# mod_hw_tb6612.net
KiCad netlist of a schematic drawn in Altium Designer
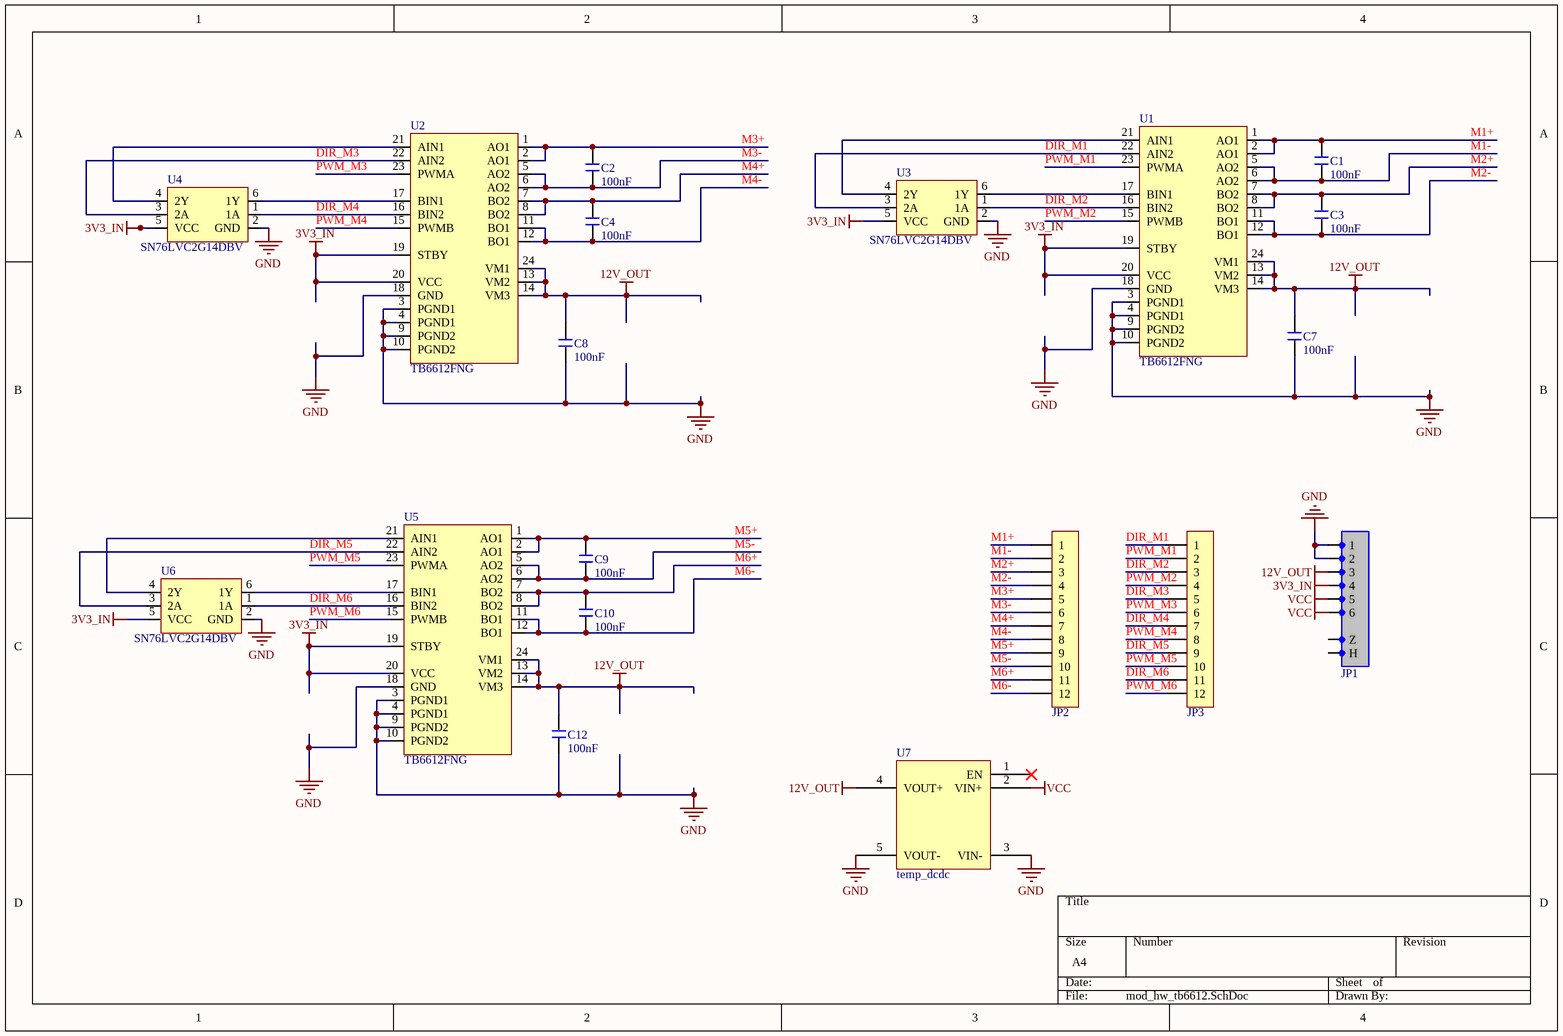
[diagram p0: mod_hw_tb6612.SchDoc]

(export (version "E")
  (design (tool "Eeschema 10.0.6"))
  (components
    (comp (ref "C1")
      (value "100nF")
      (footprint "C 0603_L")
      (description "无极性贴片电容")
      (fields (field (name "版权归属") "源创客"))
      (libsource (lib "3.2-电容") (part "C"))
    )
    (comp (ref "C2")
      (value "100nF")
      (footprint "C 0603_L")
      (description "无极性贴片电容")
      (fields (field (name "版权归属") "源创客"))
      (libsource (lib "3.2-电容") (part "C"))
    )
    (comp (ref "C3")
      (value "100nF")
      (footprint "C 0603_L")
      (description "无极性贴片电容")
      (fields (field (name "版权归属") "源创客"))
      (libsource (lib "3.2-电容") (part "C"))
    )
    (comp (ref "C4")
      (value "100nF")
      (footprint "C 0603_L")
      (description "无极性贴片电容")
      (fields (field (name "版权归属") "源创客"))
      (libsource (lib "3.2-电容") (part "C"))
    )
    (comp (ref "C7")
      (value "100nF")
      (footprint "C 1206_L")
      (description "无极性贴片电容")
      (fields (field (name "版权归属") "源创客"))
      (libsource (lib "3.2-电容") (part "C"))
    )
    (comp (ref "C8")
      (value "100nF")
      (footprint "C 1206_L")
      (description "无极性贴片电容")
      (fields (field (name "版权归属") "源创客"))
      (libsource (lib "3.2-电容") (part "C"))
    )
    (comp (ref "C9")
      (value "100nF")
      (footprint "C 0603_L")
      (description "无极性贴片电容")
      (fields (field (name "版权归属") "源创客"))
      (libsource (lib "3.2-电容") (part "C"))
    )
    (comp (ref "C10")
      (value "100nF")
      (footprint "C 0603_L")
      (description "无极性贴片电容")
      (fields (field (name "版权归属") "源创客"))
      (libsource (lib "3.2-电容") (part "C"))
    )
    (comp (ref "C12")
      (value "100nF")
      (footprint "C 1206_L")
      (description "无极性贴片电容")
      (fields (field (name "版权归属") "源创客"))
      (libsource (lib "3.2-电容") (part "C"))
    )
    (comp (ref "JP1")
      (value "HDR-1X6")
      (footprint "HDR2.54-M-LI-6P")
      (description "6P接插件")
      (fields (field (name "版权归属") "源创客"))
      (libsource (lib "14.6-接插件-脚距2.54") (part "Header 6"))
    )
    (comp (ref "JP2")
      (value "HDR-1X12")
      (footprint "HDR2.54-M-LI-12P")
      (description "12P接插件")
      (fields (field (name "版权归属") "源创客"))
      (libsource (lib "14.6-接插件-脚距2.54") (part "Header 12"))
    )
    (comp (ref "JP3")
      (value "HDR-1X12")
      (footprint "HDR2.54-M-LI-12P")
      (description "12P接插件")
      (fields (field (name "版权归属") "源创客"))
      (libsource (lib "14.6-接插件-脚距2.54") (part "Header 12"))
    )
    (comp (ref "U1")
      (value "TB6612FNG")
      (footprint "SSOP24_N")
      (libsource (lib "Schlib1") (part "Component_1"))
    )
    (comp (ref "U2")
      (value "TB6612FNG")
      (footprint "SSOP24_N")
      (libsource (lib "Schlib1") (part "Component_1"))
    )
    (comp (ref "U3")
      (value "SN76LVC2G14DBV")
      (footprint "SOT23-6N")
      (libsource (lib "Schlib1") (part "SN76LVC2G14DBV"))
    )
    (comp (ref "U4")
      (value "SN76LVC2G14DBV")
      (footprint "SOT23-6N")
      (libsource (lib "Schlib1") (part "SN76LVC2G14DBV"))
    )
    (comp (ref "U5")
      (value "TB6612FNG")
      (footprint "SSOP24_N")
      (libsource (lib "Schlib1") (part "Component_1"))
    )
    (comp (ref "U6")
      (value "SN76LVC2G14DBV")
      (footprint "SOT23-6N")
      (libsource (lib "Schlib1") (part "SN76LVC2G14DBV"))
    )
    (comp (ref "U7")
      (value "temp_dcdc")
      (footprint "TEMP_12V")
      (description "升降压模块")
      (libsource (lib "userLib") (part "temp_dcdc"))
    )
  )
  (nets
    (net (code "1") (name "/DIR_M1") (class "Default")
      (node (ref "JP3") (pin "1") (pinfunction "1_1") (pintype "passive"))
      (node (ref "U1") (pin "22") (pinfunction "AIN2_22") (pintype "passive"))
      (node (ref "U3") (pin "3") (pinfunction "2A_3") (pintype "passive"))
    )
    (net (code "2") (name "/DIR_M2") (class "Default")
      (node (ref "JP3") (pin "3") (pinfunction "3_3") (pintype "passive"))
      (node (ref "U1") (pin "16") (pinfunction "BIN2_16") (pintype "passive"))
      (node (ref "U3") (pin "1") (pinfunction "1A_1") (pintype "passive"))
    )
    (net (code "3") (name "/DIR_M3") (class "Default")
      (node (ref "JP3") (pin "5") (pinfunction "5_5") (pintype "passive"))
      (node (ref "U2") (pin "22") (pinfunction "AIN2_22") (pintype "passive"))
      (node (ref "U4") (pin "3") (pinfunction "2A_3") (pintype "passive"))
    )
    (net (code "4") (name "/DIR_M4") (class "Default")
      (node (ref "JP3") (pin "7") (pinfunction "7_7") (pintype "passive"))
      (node (ref "U2") (pin "16") (pinfunction "BIN2_16") (pintype "passive"))
      (node (ref "U4") (pin "1") (pinfunction "1A_1") (pintype "passive"))
    )
    (net (code "5") (name "/DIR_M5") (class "Default")
      (node (ref "JP3") (pin "9") (pinfunction "9_9") (pintype "passive"))
      (node (ref "U5") (pin "22") (pinfunction "AIN2_22") (pintype "passive"))
      (node (ref "U6") (pin "3") (pinfunction "2A_3") (pintype "passive"))
    )
    (net (code "6") (name "/DIR_M6") (class "Default")
      (node (ref "JP3") (pin "11") (pinfunction "11_11") (pintype "passive"))
      (node (ref "U5") (pin "16") (pinfunction "BIN2_16") (pintype "passive"))
      (node (ref "U6") (pin "1") (pinfunction "1A_1") (pintype "passive"))
    )
    (net (code "7") (name "/M1+") (class "Default")
      (node (ref "C1") (pin "2") (pinfunction "2_2") (pintype "passive"))
      (node (ref "JP2") (pin "1") (pinfunction "1_1") (pintype "passive"))
      (node (ref "U1") (pin "1") (pinfunction "AO1_1") (pintype "passive"))
      (node (ref "U1") (pin "2") (pinfunction "AO1_2") (pintype "passive"))
    )
    (net (code "8") (name "/M1-") (class "Default")
      (node (ref "C1") (pin "1") (pinfunction "1_1") (pintype "passive"))
      (node (ref "JP2") (pin "2") (pinfunction "2_2") (pintype "passive"))
      (node (ref "U1") (pin "5") (pinfunction "AO2_5") (pintype "passive"))
      (node (ref "U1") (pin "6") (pinfunction "AO2_6") (pintype "passive"))
    )
    (net (code "9") (name "/M2+") (class "Default")
      (node (ref "C3") (pin "2") (pinfunction "2_2") (pintype "passive"))
      (node (ref "JP2") (pin "3") (pinfunction "3_3") (pintype "passive"))
      (node (ref "U1") (pin "7") (pinfunction "BO2_7") (pintype "passive"))
      (node (ref "U1") (pin "8") (pinfunction "BO2_8") (pintype "passive"))
    )
    (net (code "10") (name "/M2-") (class "Default")
      (node (ref "C3") (pin "1") (pinfunction "1_1") (pintype "passive"))
      (node (ref "JP2") (pin "4") (pinfunction "4_4") (pintype "passive"))
      (node (ref "U1") (pin "11") (pinfunction "BO1_11") (pintype "passive"))
      (node (ref "U1") (pin "12") (pinfunction "BO1_12") (pintype "passive"))
    )
    (net (code "11") (name "/M3+") (class "Default")
      (node (ref "C2") (pin "2") (pinfunction "2_2") (pintype "passive"))
      (node (ref "JP2") (pin "5") (pinfunction "5_5") (pintype "passive"))
      (node (ref "U2") (pin "1") (pinfunction "AO1_1") (pintype "passive"))
      (node (ref "U2") (pin "2") (pinfunction "AO1_2") (pintype "passive"))
    )
    (net (code "12") (name "/M3-") (class "Default")
      (node (ref "C2") (pin "1") (pinfunction "1_1") (pintype "passive"))
      (node (ref "JP2") (pin "6") (pinfunction "6_6") (pintype "passive"))
      (node (ref "U2") (pin "5") (pinfunction "AO2_5") (pintype "passive"))
      (node (ref "U2") (pin "6") (pinfunction "AO2_6") (pintype "passive"))
    )
    (net (code "13") (name "/M4+") (class "Default")
      (node (ref "C4") (pin "2") (pinfunction "2_2") (pintype "passive"))
      (node (ref "JP2") (pin "7") (pinfunction "7_7") (pintype "passive"))
      (node (ref "U2") (pin "7") (pinfunction "BO2_7") (pintype "passive"))
      (node (ref "U2") (pin "8") (pinfunction "BO2_8") (pintype "passive"))
    )
    (net (code "14") (name "/M4-") (class "Default")
      (node (ref "C4") (pin "1") (pinfunction "1_1") (pintype "passive"))
      (node (ref "JP2") (pin "8") (pinfunction "8_8") (pintype "passive"))
      (node (ref "U2") (pin "11") (pinfunction "BO1_11") (pintype "passive"))
      (node (ref "U2") (pin "12") (pinfunction "BO1_12") (pintype "passive"))
    )
    (net (code "15") (name "/M5+") (class "Default")
      (node (ref "C9") (pin "2") (pinfunction "2_2") (pintype "passive"))
      (node (ref "JP2") (pin "9") (pinfunction "9_9") (pintype "passive"))
      (node (ref "U5") (pin "1") (pinfunction "AO1_1") (pintype "passive"))
      (node (ref "U5") (pin "2") (pinfunction "AO1_2") (pintype "passive"))
    )
    (net (code "16") (name "/M5-") (class "Default")
      (node (ref "C9") (pin "1") (pinfunction "1_1") (pintype "passive"))
      (node (ref "JP2") (pin "10") (pinfunction "10_10") (pintype "passive"))
      (node (ref "U5") (pin "5") (pinfunction "AO2_5") (pintype "passive"))
      (node (ref "U5") (pin "6") (pinfunction "AO2_6") (pintype "passive"))
    )
    (net (code "17") (name "/M6+") (class "Default")
      (node (ref "C10") (pin "2") (pinfunction "2_2") (pintype "passive"))
      (node (ref "JP2") (pin "11") (pinfunction "11_11") (pintype "passive"))
      (node (ref "U5") (pin "7") (pinfunction "BO2_7") (pintype "passive"))
      (node (ref "U5") (pin "8") (pinfunction "BO2_8") (pintype "passive"))
    )
    (net (code "18") (name "/M6-") (class "Default")
      (node (ref "C10") (pin "1") (pinfunction "1_1") (pintype "passive"))
      (node (ref "JP2") (pin "12") (pinfunction "12_12") (pintype "passive"))
      (node (ref "U5") (pin "11") (pinfunction "BO1_11") (pintype "passive"))
      (node (ref "U5") (pin "12") (pinfunction "BO1_12") (pintype "passive"))
    )
    (net (code "19") (name "/PWM_M1") (class "Default")
      (node (ref "JP3") (pin "2") (pinfunction "2_2") (pintype "passive"))
      (node (ref "U1") (pin "23") (pinfunction "PWMA_23") (pintype "passive"))
    )
    (net (code "20") (name "/PWM_M2") (class "Default")
      (node (ref "JP3") (pin "4") (pinfunction "4_4") (pintype "passive"))
      (node (ref "U1") (pin "15") (pinfunction "PWMB_15") (pintype "passive"))
    )
    (net (code "21") (name "/PWM_M3") (class "Default")
      (node (ref "JP3") (pin "6") (pinfunction "6_6") (pintype "passive"))
      (node (ref "U2") (pin "23") (pinfunction "PWMA_23") (pintype "passive"))
    )
    (net (code "22") (name "/PWM_M4") (class "Default")
      (node (ref "JP3") (pin "8") (pinfunction "8_8") (pintype "passive"))
      (node (ref "U2") (pin "15") (pinfunction "PWMB_15") (pintype "passive"))
    )
    (net (code "23") (name "/PWM_M5") (class "Default")
      (node (ref "JP3") (pin "10") (pinfunction "10_10") (pintype "passive"))
      (node (ref "U5") (pin "23") (pinfunction "PWMA_23") (pintype "passive"))
    )
    (net (code "24") (name "/PWM_M6") (class "Default")
      (node (ref "JP3") (pin "12") (pinfunction "12_12") (pintype "passive"))
      (node (ref "U5") (pin "15") (pinfunction "PWMB_15") (pintype "passive"))
    )
    (net (code "25") (name "3V3_IN") (class "Default")
      (node (ref "JP1") (pin "4") (pinfunction "4_4") (pintype "passive"))
      (node (ref "U1") (pin "19") (pinfunction "STBY_19") (pintype "passive"))
      (node (ref "U1") (pin "20") (pinfunction "VCC_20") (pintype "passive"))
      (node (ref "U2") (pin "19") (pinfunction "STBY_19") (pintype "passive"))
      (node (ref "U2") (pin "20") (pinfunction "VCC_20") (pintype "passive"))
      (node (ref "U3") (pin "5") (pinfunction "VCC_5") (pintype "passive"))
      (node (ref "U4") (pin "5") (pinfunction "VCC_5") (pintype "passive"))
      (node (ref "U5") (pin "19") (pinfunction "STBY_19") (pintype "passive"))
      (node (ref "U5") (pin "20") (pinfunction "VCC_20") (pintype "passive"))
      (node (ref "U6") (pin "5") (pinfunction "VCC_5") (pintype "passive"))
    )
    (net (code "26") (name "12V_OUT") (class "Default")
      (node (ref "C12") (pin "2") (pinfunction "2_2") (pintype "passive"))
      (node (ref "C7") (pin "2") (pinfunction "2_2") (pintype "passive"))
      (node (ref "C8") (pin "2") (pinfunction "2_2") (pintype "passive"))
      (node (ref "JP1") (pin "3") (pinfunction "3_3") (pintype "passive"))
      (node (ref "U1") (pin "13") (pinfunction "VM2_13") (pintype "passive"))
      (node (ref "U1") (pin "14") (pinfunction "VM3_14") (pintype "passive"))
      (node (ref "U1") (pin "24") (pinfunction "VM1_24") (pintype "passive"))
      (node (ref "U2") (pin "13") (pinfunction "VM2_13") (pintype "passive"))
      (node (ref "U2") (pin "14") (pinfunction "VM3_14") (pintype "passive"))
      (node (ref "U2") (pin "24") (pinfunction "VM1_24") (pintype "passive"))
      (node (ref "U5") (pin "13") (pinfunction "VM2_13") (pintype "passive"))
      (node (ref "U5") (pin "14") (pinfunction "VM3_14") (pintype "passive"))
      (node (ref "U5") (pin "24") (pinfunction "VM1_24") (pintype "passive"))
      (node (ref "U7") (pin "4") (pinfunction "VOUT+_4") (pintype "passive"))
    )
    (net (code "27") (name "GND") (class "Default")
      (node (ref "C12") (pin "1") (pinfunction "1_1") (pintype "passive"))
      (node (ref "C7") (pin "1") (pinfunction "1_1") (pintype "passive"))
      (node (ref "C8") (pin "1") (pinfunction "1_1") (pintype "passive"))
      (node (ref "JP1") (pin "1") (pinfunction "1_1") (pintype "passive"))
      (node (ref "JP1") (pin "2") (pinfunction "2_2") (pintype "passive"))
      (node (ref "U1") (pin "10") (pinfunction "PGND2_10") (pintype "passive"))
      (node (ref "U1") (pin "18") (pinfunction "GND_18") (pintype "passive"))
      (node (ref "U1") (pin "3") (pinfunction "PGND1_3") (pintype "passive"))
      (node (ref "U1") (pin "4") (pinfunction "PGND1_4") (pintype "passive"))
      (node (ref "U1") (pin "9") (pinfunction "PGND2_9") (pintype "passive"))
      (node (ref "U2") (pin "10") (pinfunction "PGND2_10") (pintype "passive"))
      (node (ref "U2") (pin "18") (pinfunction "GND_18") (pintype "passive"))
      (node (ref "U2") (pin "3") (pinfunction "PGND1_3") (pintype "passive"))
      (node (ref "U2") (pin "4") (pinfunction "PGND1_4") (pintype "passive"))
      (node (ref "U2") (pin "9") (pinfunction "PGND2_9") (pintype "passive"))
      (node (ref "U3") (pin "2") (pinfunction "GND_2") (pintype "passive"))
      (node (ref "U4") (pin "2") (pinfunction "GND_2") (pintype "passive"))
      (node (ref "U5") (pin "10") (pinfunction "PGND2_10") (pintype "passive"))
      (node (ref "U5") (pin "18") (pinfunction "GND_18") (pintype "passive"))
      (node (ref "U5") (pin "3") (pinfunction "PGND1_3") (pintype "passive"))
      (node (ref "U5") (pin "4") (pinfunction "PGND1_4") (pintype "passive"))
      (node (ref "U5") (pin "9") (pinfunction "PGND2_9") (pintype "passive"))
      (node (ref "U6") (pin "2") (pinfunction "GND_2") (pintype "passive"))
      (node (ref "U7") (pin "3") (pinfunction "VIN-_3") (pintype "passive"))
      (node (ref "U7") (pin "5") (pinfunction "VOUT-_5") (pintype "passive"))
    )
    (net (code "28") (name "Net-(U1-AIN1)") (class "Default")
      (node (ref "U1") (pin "21") (pinfunction "AIN1_21") (pintype "passive"))
      (node (ref "U3") (pin "4") (pinfunction "2Y_4") (pintype "passive"))
    )
    (net (code "29") (name "Net-(U1-BIN1)") (class "Default")
      (node (ref "U1") (pin "17") (pinfunction "BIN1_17") (pintype "passive"))
      (node (ref "U3") (pin "6") (pinfunction "1Y_6") (pintype "passive"))
    )
    (net (code "30") (name "Net-(U2-AIN1)") (class "Default")
      (node (ref "U2") (pin "21") (pinfunction "AIN1_21") (pintype "passive"))
      (node (ref "U4") (pin "4") (pinfunction "2Y_4") (pintype "passive"))
    )
    (net (code "31") (name "Net-(U2-BIN1)") (class "Default")
      (node (ref "U2") (pin "17") (pinfunction "BIN1_17") (pintype "passive"))
      (node (ref "U4") (pin "6") (pinfunction "1Y_6") (pintype "passive"))
    )
    (net (code "32") (name "Net-(U5-AIN1)") (class "Default")
      (node (ref "U5") (pin "21") (pinfunction "AIN1_21") (pintype "passive"))
      (node (ref "U6") (pin "4") (pinfunction "2Y_4") (pintype "passive"))
    )
    (net (code "33") (name "Net-(U5-BIN1)") (class "Default")
      (node (ref "U5") (pin "17") (pinfunction "BIN1_17") (pintype "passive"))
      (node (ref "U6") (pin "6") (pinfunction "1Y_6") (pintype "passive"))
    )
    (net (code "34") (name "VCC") (class "Default")
      (node (ref "JP1") (pin "5") (pinfunction "5_5") (pintype "passive"))
      (node (ref "JP1") (pin "6") (pinfunction "6_6") (pintype "passive"))
      (node (ref "U7") (pin "2") (pinfunction "VIN+_2") (pintype "passive"))
    )
    (net (code "35") (name "unconnected-(JP1-H-Pad100)") (class "Default")
      (node (ref "JP1") (pin "100") (pinfunction "H_100") (pintype "passive"))
    )
    (net (code "36") (name "unconnected-(JP1-Z-Pad0)") (class "Default")
      (node (ref "JP1") (pin "0") (pinfunction "Z_0") (pintype "passive"))
    )
    (net (code "37") (name "unconnected-(U7-EN-Pad1)") (class "Default")
      (node (ref "U7") (pin "1") (pinfunction "EN_1") (pintype "passive+no_connect"))
    )
  )
)
